# twitterer.net
KiCad netlist of a schematic drawn in EAGLE
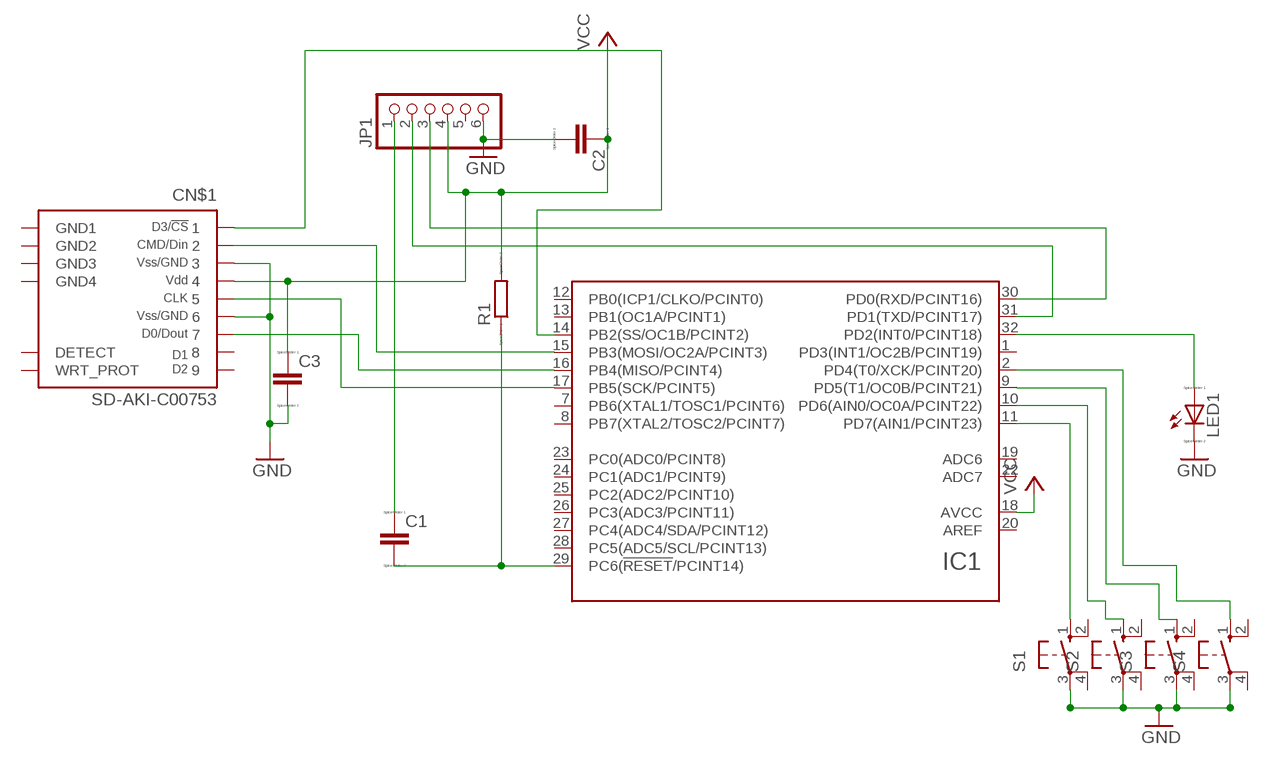
[diagram p0: schematic, sheet 1]

(export (version "E")
  (design (tool "Eeschema 10.0.6"))
  (components
    (comp (ref "C1")
      (value "CC0603")
      (footprint "eagle-import:C0603")
      (libsource (lib "eagle-import") (part "CC0603"))
    )
    (comp (ref "C2")
      (value "CC0603")
      (footprint "eagle-import:C0603")
      (libsource (lib "eagle-import") (part "CC0603"))
    )
    (comp (ref "C3")
      (value "CC0603")
      (footprint "eagle-import:C0603")
      (libsource (lib "eagle-import") (part "CC0603"))
    )
    (comp (ref "CN$1")
      (value "SD-AKI-C00753")
      (footprint "eagle-import:C-1734234")
      (libsource (lib "eagle-import") (part "SD-AKI-C00753"))
    )
    (comp (ref "IC1")
      (value "ATMEGA48/88/168/328-AU")
      (footprint "eagle-import:TQFP32-08")
      (libsource (lib "eagle-import") (part "ATMEGA48/88/168/328-AU"))
    )
    (comp (ref "JP1")
      (value "PINHD-1X6")
      (footprint "eagle-import:1X06")
      (libsource (lib "eagle-import") (part "PINHD-1X6"))
    )
    (comp (ref "LED1")
      (value "LED_ELD260")
      (footprint "eagle-import:LED_LD260")
      (libsource (lib "eagle-import") (part "LED_ELD260"))
    )
    (comp (ref "R1")
      (value "RR0603")
      (footprint "eagle-import:R0603")
      (libsource (lib "eagle-import") (part "RR0603"))
    )
    (comp (ref "S1")
      (value "10-XX")
      (footprint "eagle-import:B3F-10XX")
      (fields (field (name "MPN") "B3F-1000"))
      (libsource (lib "eagle-import") (part "10-XX"))
    )
    (comp (ref "S2")
      (value "10-XX")
      (footprint "eagle-import:B3F-10XX")
      (fields (field (name "MPN") "B3F-1000"))
      (libsource (lib "eagle-import") (part "10-XX"))
    )
    (comp (ref "S3")
      (value "10-XX")
      (footprint "eagle-import:B3F-10XX")
      (fields (field (name "MPN") "B3F-1000"))
      (libsource (lib "eagle-import") (part "10-XX"))
    )
    (comp (ref "S4")
      (value "10-XX")
      (footprint "eagle-import:B3F-10XX")
      (fields (field (name "MPN") "B3F-1000"))
      (libsource (lib "eagle-import") (part "10-XX"))
    )
  )
  (nets
    (net (code "1") (name "/GND1") (class "Default")
      (node (ref "CN$1") (pin "GND1") (pinfunction "GND1_GND1") (pintype "power_in"))
    )
    (net (code "2") (name "/GND2") (class "Default")
      (node (ref "CN$1") (pin "GND2") (pinfunction "GND2_GND2") (pintype "power_in"))
    )
    (net (code "3") (name "/GND3") (class "Default")
      (node (ref "CN$1") (pin "GND3") (pinfunction "GND3_GND3") (pintype "power_in"))
    )
    (net (code "4") (name "/GND4") (class "Default")
      (node (ref "CN$1") (pin "GND4") (pinfunction "GND4_GND4") (pintype "power_in"))
    )
    (net (code "5") (name "GND") (class "Default")
      (node (ref "C2") (pin "2") (pinfunction "2_2") (pintype "passive"))
      (node (ref "C3") (pin "2") (pinfunction "2_2") (pintype "passive"))
      (node (ref "CN$1") (pin "3") (pinfunction "3_3") (pintype "power_in"))
      (node (ref "CN$1") (pin "6") (pinfunction "6_6") (pintype "power_in"))
      (node (ref "JP1") (pin "6") (pinfunction "6_6") (pintype "passive"))
      (node (ref "LED1") (pin "K") (pinfunction "C_K") (pintype "passive"))
      (node (ref "S1") (pin "3") (pinfunction "P_3") (pintype "passive"))
      (node (ref "S2") (pin "3") (pinfunction "P_3") (pintype "passive"))
      (node (ref "S3") (pin "3") (pinfunction "P_3") (pintype "passive"))
      (node (ref "S4") (pin "3") (pinfunction "P_3") (pintype "passive"))
    )
    (net (code "6") (name "Net-(C1-Pad1)") (class "Default")
      (node (ref "C1") (pin "1") (pinfunction "1_1") (pintype "passive"))
      (node (ref "JP1") (pin "1") (pinfunction "1_1") (pintype "passive"))
    )
    (net (code "7") (name "Net-(IC1A-PB2(SS{slash}OC1B{slash}PCINT2))") (class "Default")
      (node (ref "CN$1") (pin "1") (pinfunction "1_1") (pintype "bidirectional"))
      (node (ref "IC1") (pin "14") (pinfunction "PB2(SS/OC1B/PCINT2)_14") (pintype "bidirectional"))
    )
    (net (code "8") (name "Net-(IC1A-PB3(MOSI{slash}OC2A{slash}PCINT3))") (class "Default")
      (node (ref "CN$1") (pin "2") (pinfunction "2_2") (pintype "input"))
      (node (ref "IC1") (pin "15") (pinfunction "PB3(MOSI/OC2A/PCINT3)_15") (pintype "bidirectional"))
    )
    (net (code "9") (name "Net-(IC1A-PB4(MISO{slash}PCINT4))") (class "Default")
      (node (ref "CN$1") (pin "7") (pinfunction "7_7") (pintype "bidirectional"))
      (node (ref "IC1") (pin "16") (pinfunction "PB4(MISO/PCINT4)_16") (pintype "bidirectional"))
    )
    (net (code "10") (name "Net-(IC1A-PB5(SCK{slash}PCINT5))") (class "Default")
      (node (ref "CN$1") (pin "5") (pinfunction "5_5") (pintype "input"))
      (node (ref "IC1") (pin "17") (pinfunction "PB5(SCK/PCINT5)_17") (pintype "bidirectional"))
    )
    (net (code "11") (name "Net-(IC1A-PC6(~{RESET}{slash}PCINT14))") (class "Default")
      (node (ref "C1") (pin "2") (pinfunction "2_2") (pintype "passive"))
      (node (ref "IC1") (pin "29") (pinfunction "PC6(~{RESET}/PCINT14)_29") (pintype "bidirectional"))
      (node (ref "R1") (pin "1") (pinfunction "1_1") (pintype "passive"))
    )
    (net (code "12") (name "Net-(IC1A-PD0(RXD{slash}PCINT16))") (class "Default")
      (node (ref "IC1") (pin "30") (pinfunction "PD0(RXD/PCINT16)_30") (pintype "bidirectional"))
      (node (ref "JP1") (pin "3") (pinfunction "3_3") (pintype "passive"))
    )
    (net (code "13") (name "Net-(IC1A-PD1(TXD{slash}PCINT17))") (class "Default")
      (node (ref "IC1") (pin "31") (pinfunction "PD1(TXD/PCINT17)_31") (pintype "bidirectional"))
      (node (ref "JP1") (pin "2") (pinfunction "2_2") (pintype "passive"))
    )
    (net (code "14") (name "Net-(IC1A-PD2(INT0{slash}PCINT18))") (class "Default")
      (node (ref "IC1") (pin "32") (pinfunction "PD2(INT0/PCINT18)_32") (pintype "bidirectional"))
      (node (ref "LED1") (pin "A") (pinfunction "A_A") (pintype "passive"))
    )
    (net (code "15") (name "Net-(IC1A-PD4(T0{slash}XCK{slash}PCINT20))") (class "Default")
      (node (ref "IC1") (pin "2") (pinfunction "PD4(T0/XCK/PCINT20)_2") (pintype "bidirectional"))
      (node (ref "S4") (pin "1") (pinfunction "S_1") (pintype "passive"))
    )
    (net (code "16") (name "Net-(IC1A-PD5(T1{slash}OC0B{slash}PCINT21))") (class "Default")
      (node (ref "IC1") (pin "9") (pinfunction "PD5(T1/OC0B/PCINT21)_9") (pintype "bidirectional"))
      (node (ref "S3") (pin "1") (pinfunction "S_1") (pintype "passive"))
    )
    (net (code "17") (name "Net-(IC1A-PD6(AIN0{slash}OC0A{slash}PCINT22))") (class "Default")
      (node (ref "IC1") (pin "10") (pinfunction "PD6(AIN0/OC0A/PCINT22)_10") (pintype "bidirectional"))
      (node (ref "S2") (pin "1") (pinfunction "S_1") (pintype "passive"))
    )
    (net (code "18") (name "Net-(IC1A-PD7(AIN1{slash}PCINT23))") (class "Default")
      (node (ref "IC1") (pin "11") (pinfunction "PD7(AIN1/PCINT23)_11") (pintype "bidirectional"))
      (node (ref "S1") (pin "1") (pinfunction "S_1") (pintype "passive"))
    )
    (net (code "19") (name "VCC") (class "Default")
      (node (ref "C2") (pin "1") (pinfunction "1_1") (pintype "passive"))
      (node (ref "C3") (pin "1") (pinfunction "1_1") (pintype "passive"))
      (node (ref "CN$1") (pin "4") (pinfunction "4_4") (pintype "power_in"))
      (node (ref "IC1") (pin "18") (pinfunction "AVCC_18") (pintype "power_in"))
      (node (ref "JP1") (pin "4") (pinfunction "4_4") (pintype "passive"))
      (node (ref "R1") (pin "2") (pinfunction "2_2") (pintype "passive"))
    )
    (net (code "20") (name "unconnected-(CN$1-Pad8)") (class "Default")
      (node (ref "CN$1") (pin "8") (pinfunction "8_8") (pintype "bidirectional"))
    )
    (net (code "21") (name "unconnected-(CN$1-Pad9)") (class "Default")
      (node (ref "CN$1") (pin "9") (pinfunction "9_9") (pintype "bidirectional"))
    )
    (net (code "22") (name "unconnected-(CN$1-PadDETECT)") (class "Default")
      (node (ref "CN$1") (pin "DETECT") (pinfunction "DETECT_DETECT") (pintype "output"))
    )
    (net (code "23") (name "unconnected-(CN$1-PadWRT_PROT)") (class "Default")
      (node (ref "CN$1") (pin "WRT_PROT") (pinfunction "WRT_PROT_WRT_PROT") (pintype "output"))
    )
    (net (code "24") (name "unconnected-(IC1A-ADC6-Pad19)") (class "Default")
      (node (ref "IC1") (pin "19") (pinfunction "ADC6_19") (pintype "passive"))
    )
    (net (code "25") (name "unconnected-(IC1A-ADC7-Pad22)") (class "Default")
      (node (ref "IC1") (pin "22") (pinfunction "ADC7_22") (pintype "passive"))
    )
    (net (code "26") (name "unconnected-(IC1A-AREF-Pad20)") (class "Default")
      (node (ref "IC1") (pin "20") (pinfunction "AREF_20") (pintype "passive"))
    )
    (net (code "27") (name "unconnected-(IC1A-PB0(ICP1{slash}CLKO{slash}PCINT0)-Pad12)") (class "Default")
      (node (ref "IC1") (pin "12") (pinfunction "PB0(ICP1/CLKO/PCINT0)_12") (pintype "bidirectional"))
    )
    (net (code "28") (name "unconnected-(IC1A-PB1(OC1A{slash}PCINT1)-Pad13)") (class "Default")
      (node (ref "IC1") (pin "13") (pinfunction "PB1(OC1A/PCINT1)_13") (pintype "bidirectional"))
    )
    (net (code "29") (name "unconnected-(IC1A-PB6(XTAL1{slash}TOSC1{slash}PCINT6)-Pad7)") (class "Default")
      (node (ref "IC1") (pin "7") (pinfunction "PB6(XTAL1/TOSC1/PCINT6)_7") (pintype "bidirectional"))
    )
    (net (code "30") (name "unconnected-(IC1A-PB7(XTAL2{slash}TOSC2{slash}PCINT7)-Pad8)") (class "Default")
      (node (ref "IC1") (pin "8") (pinfunction "PB7(XTAL2/TOSC2/PCINT7)_8") (pintype "bidirectional"))
    )
    (net (code "31") (name "unconnected-(IC1A-PC0(ADC0{slash}PCINT8)-Pad23)") (class "Default")
      (node (ref "IC1") (pin "23") (pinfunction "PC0(ADC0/PCINT8)_23") (pintype "bidirectional"))
    )
    (net (code "32") (name "unconnected-(IC1A-PC1(ADC1{slash}PCINT9)-Pad24)") (class "Default")
      (node (ref "IC1") (pin "24") (pinfunction "PC1(ADC1/PCINT9)_24") (pintype "bidirectional"))
    )
    (net (code "33") (name "unconnected-(IC1A-PC2(ADC2{slash}PCINT10)-Pad25)") (class "Default")
      (node (ref "IC1") (pin "25") (pinfunction "PC2(ADC2/PCINT10)_25") (pintype "bidirectional"))
    )
    (net (code "34") (name "unconnected-(IC1A-PC3(ADC3{slash}PCINT11)-Pad26)") (class "Default")
      (node (ref "IC1") (pin "26") (pinfunction "PC3(ADC3/PCINT11)_26") (pintype "bidirectional"))
    )
    (net (code "35") (name "unconnected-(IC1A-PC4(ADC4{slash}SDA{slash}PCINT12)-Pad27)") (class "Default")
      (node (ref "IC1") (pin "27") (pinfunction "PC4(ADC4/SDA/PCINT12)_27") (pintype "bidirectional"))
    )
    (net (code "36") (name "unconnected-(IC1A-PC5(ADC5{slash}SCL{slash}PCINT13)-Pad28)") (class "Default")
      (node (ref "IC1") (pin "28") (pinfunction "PC5(ADC5/SCL/PCINT13)_28") (pintype "bidirectional"))
    )
    (net (code "37") (name "unconnected-(IC1A-PD3(INT1{slash}OC2B{slash}PCINT19)-Pad1)") (class "Default")
      (node (ref "IC1") (pin "1") (pinfunction "PD3(INT1/OC2B/PCINT19)_1") (pintype "bidirectional"))
    )
    (net (code "38") (name "unconnected-(JP1-Pad5)") (class "Default")
      (node (ref "JP1") (pin "5") (pinfunction "5_5") (pintype "passive"))
    )
    (net (code "39") (name "unconnected-(S1-P1-Pad4)") (class "Default")
      (node (ref "S1") (pin "4") (pinfunction "P1_4") (pintype "passive"))
    )
    (net (code "40") (name "unconnected-(S1-S1-Pad2)") (class "Default")
      (node (ref "S1") (pin "2") (pinfunction "S1_2") (pintype "passive"))
    )
    (net (code "41") (name "unconnected-(S2-P1-Pad4)") (class "Default")
      (node (ref "S2") (pin "4") (pinfunction "P1_4") (pintype "passive"))
    )
    (net (code "42") (name "unconnected-(S2-S1-Pad2)") (class "Default")
      (node (ref "S2") (pin "2") (pinfunction "S1_2") (pintype "passive"))
    )
    (net (code "43") (name "unconnected-(S3-P1-Pad4)") (class "Default")
      (node (ref "S3") (pin "4") (pinfunction "P1_4") (pintype "passive"))
    )
    (net (code "44") (name "unconnected-(S3-S1-Pad2)") (class "Default")
      (node (ref "S3") (pin "2") (pinfunction "S1_2") (pintype "passive"))
    )
    (net (code "45") (name "unconnected-(S4-P1-Pad4)") (class "Default")
      (node (ref "S4") (pin "4") (pinfunction "P1_4") (pintype "passive"))
    )
    (net (code "46") (name "unconnected-(S4-S1-Pad2)") (class "Default")
      (node (ref "S4") (pin "2") (pinfunction "S1_2") (pintype "passive"))
    )
  )
)
